# NeuroWing.net
KiCad netlist of a schematic drawn in EAGLE
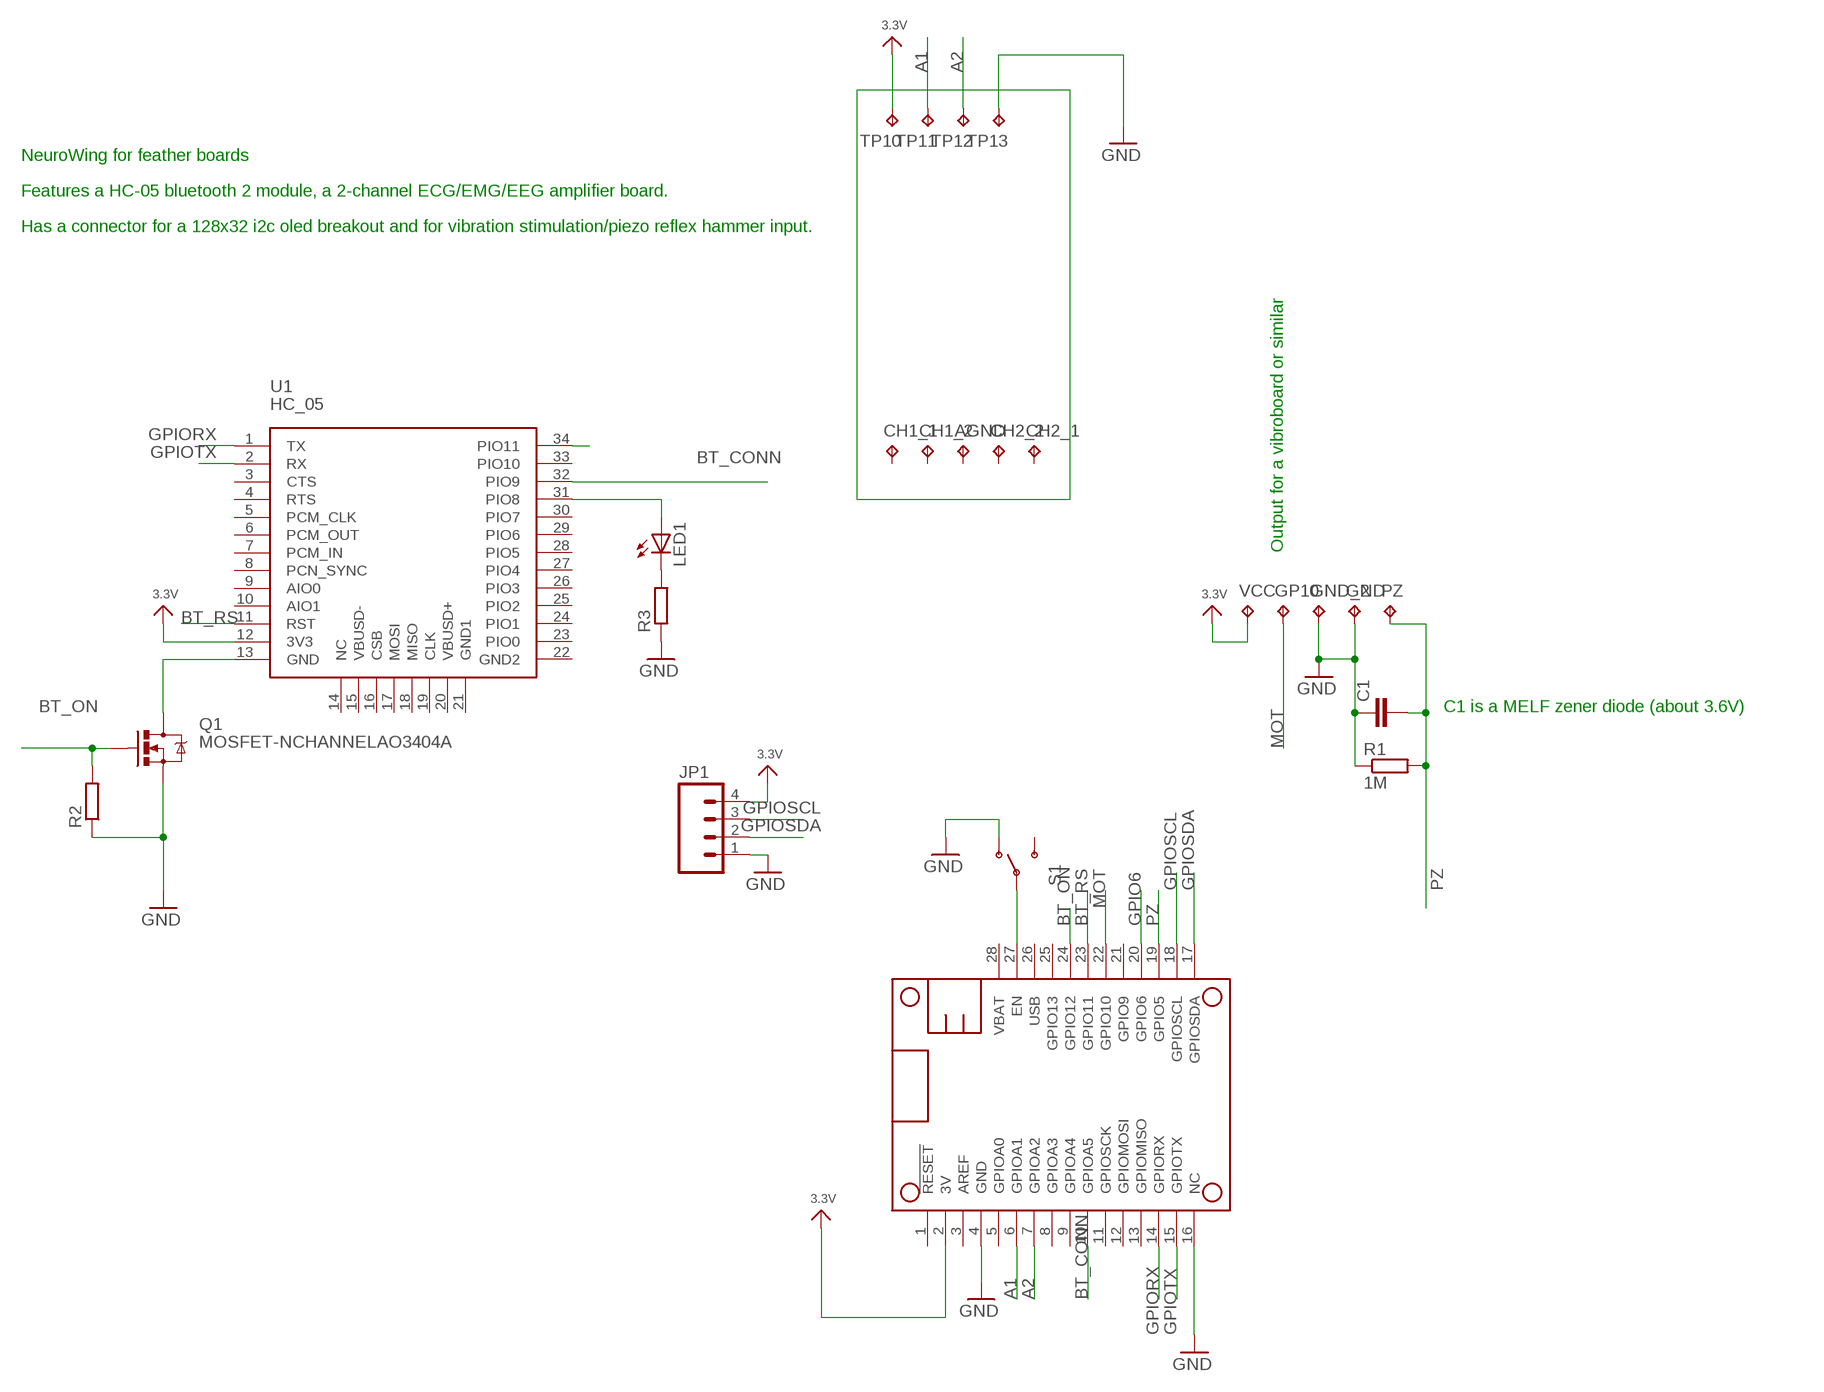
[diagram p0: schematic, sheet 1]

(export (version "E")
  (design (tool "Eeschema 10.0.6"))
  (components
    (comp (ref "AGND")
      (value "TPTP17R")
      (footprint "eagle-import:TP17R")
      (libsource (lib "eagle-import") (part "TPTP17R"))
    )
    (comp (ref "C1")
      (value "C-EUC1206")
      (footprint "eagle-import:C1206")
      (libsource (lib "eagle-import") (part "C-EUC1206"))
    )
    (comp (ref "CH1_1")
      (value "TPTP17R")
      (footprint "eagle-import:TP17R")
      (libsource (lib "eagle-import") (part "TPTP17R"))
    )
    (comp (ref "CH1_2")
      (value "TPTP17R")
      (footprint "eagle-import:TP17R")
      (libsource (lib "eagle-import") (part "TPTP17R"))
    )
    (comp (ref "CH2_1")
      (value "TPTP17R")
      (footprint "eagle-import:TP17R")
      (libsource (lib "eagle-import") (part "TPTP17R"))
    )
    (comp (ref "CH2_2")
      (value "TPTP17R")
      (footprint "eagle-import:TP17R")
      (libsource (lib "eagle-import") (part "TPTP17R"))
    )
    (comp (ref "GND")
      (value "TPTP20R")
      (footprint "eagle-import:TP20R")
      (libsource (lib "eagle-import") (part "TPTP20R"))
    )
    (comp (ref "GND_2")
      (value "TPTP20R")
      (footprint "eagle-import:TP20R")
      (libsource (lib "eagle-import") (part "TPTP20R"))
    )
    (comp (ref "GP10")
      (value "TPTP20R")
      (footprint "eagle-import:TP20R")
      (libsource (lib "eagle-import") (part "TPTP20R"))
    )
    (comp (ref "JP1")
      (value "M04PTH")
      (footprint "eagle-import:1X04")
      (libsource (lib "eagle-import") (part "M04PTH"))
    )
    (comp (ref "LED1")
      (value "LEDCHIP-LED0805")
      (footprint "eagle-import:CHIP-LED0805")
      (libsource (lib "eagle-import") (part "LEDCHIP-LED0805"))
    )
    (comp (ref "MS2")
      (value "FEATHERWING")
      (footprint "eagle-import:FEATHERWING")
      (libsource (lib "eagle-import") (part "FEATHERWING"))
    )
    (comp (ref "PZ")
      (value "TPTP20R")
      (footprint "eagle-import:TP20R")
      (libsource (lib "eagle-import") (part "TPTP20R"))
    )
    (comp (ref "Q1")
      (value "MOSFET-NCHANNELAO3404A")
      (footprint "eagle-import:SOT23-3")
      (libsource (lib "eagle-import") (part "MOSFET-NCHANNELAO3404A"))
    )
    (comp (ref "R1")
      (value "1M")
      (footprint "eagle-import:R0603")
      (libsource (lib "eagle-import") (part "R-EU_R0603"))
    )
    (comp (ref "R2")
      (value "R-EU_R0603")
      (footprint "eagle-import:R0603")
      (libsource (lib "eagle-import") (part "R-EU_R0603"))
    )
    (comp (ref "R3")
      (value "R-EU_R0603")
      (footprint "eagle-import:R0603")
      (libsource (lib "eagle-import") (part "R-EU_R0603"))
    )
    (comp (ref "S1")
      (value "SWITCH-SPDT-SMD-A")
      (footprint "eagle-import:SWITCH-SPST-SMD-A")
      (libsource (lib "eagle-import") (part "SWITCH-SPDT-SMD-A"))
    )
    (comp (ref "TP10")
      (value "TPTP17R")
      (footprint "eagle-import:TP17R")
      (libsource (lib "eagle-import") (part "TPTP17R"))
    )
    (comp (ref "TP11")
      (value "TPTP17R")
      (footprint "eagle-import:TP17R")
      (libsource (lib "eagle-import") (part "TPTP17R"))
    )
    (comp (ref "TP12")
      (value "TPTP17R")
      (footprint "eagle-import:TP17R")
      (libsource (lib "eagle-import") (part "TPTP17R"))
    )
    (comp (ref "TP13")
      (value "TPTP17R")
      (footprint "eagle-import:TP17R")
      (libsource (lib "eagle-import") (part "TPTP17R"))
    )
    (comp (ref "U1")
      (value "HC_05")
      (footprint "eagle-import:BLUETOOTH_SMD")
      (libsource (lib "eagle-import") (part "HC_05"))
    )
    (comp (ref "VCC")
      (value "TPTP20R")
      (footprint "eagle-import:TP20R")
      (libsource (lib "eagle-import") (part "TPTP20R"))
    )
  )
  (nets
    (net (code "1") (name "/A1") (class "Default")
      (node (ref "MS2") (pin "6") (pinfunction "GPIOA1_6") (pintype "bidirectional"))
      (node (ref "TP11") (pin "TP") (pinfunction "TP_TP") (pintype "input"))
    )
    (net (code "2") (name "/A2") (class "Default")
      (node (ref "MS2") (pin "7") (pinfunction "GPIOA2_7") (pintype "bidirectional"))
      (node (ref "TP12") (pin "TP") (pinfunction "TP_TP") (pintype "input"))
    )
    (net (code "3") (name "/BT_CONN") (class "Default")
      (node (ref "MS2") (pin "10") (pinfunction "GPIOA5_10") (pintype "bidirectional"))
      (node (ref "U1") (pin "32") (pinfunction "PIO9_32") (pintype "bidirectional"))
    )
    (net (code "4") (name "/BT_ON") (class "Default")
      (node (ref "MS2") (pin "24") (pinfunction "GPIO12_24") (pintype "bidirectional"))
      (node (ref "Q1") (pin "1") (pinfunction "G_1") (pintype "passive"))
      (node (ref "R2") (pin "2") (pinfunction "2_2") (pintype "passive"))
    )
    (net (code "5") (name "/BT_RS") (class "Default")
      (node (ref "MS2") (pin "23") (pinfunction "GPIO11_23") (pintype "bidirectional"))
      (node (ref "U1") (pin "11") (pinfunction "RST_11") (pintype "bidirectional"))
    )
    (net (code "6") (name "/GPIO6") (class "Default")
      (node (ref "MS2") (pin "20") (pinfunction "GPIO6_20") (pintype "bidirectional"))
    )
    (net (code "7") (name "/GPIORX") (class "Default")
      (node (ref "MS2") (pin "14") (pinfunction "GPIORX_14") (pintype "bidirectional"))
      (node (ref "U1") (pin "1") (pinfunction "TX_1") (pintype "bidirectional"))
    )
    (net (code "8") (name "/GPIOSCL") (class "Default")
      (node (ref "JP1") (pin "3") (pinfunction "3_3") (pintype "passive"))
      (node (ref "MS2") (pin "18") (pinfunction "GPIOSCL_18") (pintype "bidirectional"))
    )
    (net (code "9") (name "/GPIOSDA") (class "Default")
      (node (ref "JP1") (pin "2") (pinfunction "2_2") (pintype "passive"))
      (node (ref "MS2") (pin "17") (pinfunction "GPIOSDA_17") (pintype "bidirectional"))
    )
    (net (code "10") (name "/GPIOTX") (class "Default")
      (node (ref "MS2") (pin "15") (pinfunction "GPIOTX_15") (pintype "bidirectional"))
      (node (ref "U1") (pin "2") (pinfunction "RX_2") (pintype "bidirectional"))
    )
    (net (code "11") (name "/MOT") (class "Default")
      (node (ref "GP10") (pin "TP") (pinfunction "TP_TP") (pintype "input"))
      (node (ref "MS2") (pin "22") (pinfunction "GPIO10_22") (pintype "bidirectional"))
    )
    (net (code "12") (name "/PZ") (class "Default")
      (node (ref "C1") (pin "2") (pinfunction "2_2") (pintype "passive"))
      (node (ref "MS2") (pin "19") (pinfunction "GPIO5_19") (pintype "bidirectional"))
      (node (ref "PZ") (pin "TP") (pinfunction "TP_TP") (pintype "input"))
      (node (ref "R1") (pin "2") (pinfunction "2_2") (pintype "passive"))
    )
    (net (code "13") (name "/USB") (class "Default")
      (node (ref "MS2") (pin "26") (pinfunction "USB_26") (pintype "power_in"))
    )
    (net (code "14") (name "/VBAT") (class "Default")
      (node (ref "MS2") (pin "28") (pinfunction "VBAT_28") (pintype "power_in"))
    )
    (net (code "15") (name "3.3V") (class "Default")
      (node (ref "JP1") (pin "4") (pinfunction "4_4") (pintype "passive"))
      (node (ref "MS2") (pin "2") (pinfunction "3V_2") (pintype "power_in"))
      (node (ref "TP10") (pin "TP") (pinfunction "TP_TP") (pintype "input"))
      (node (ref "U1") (pin "12") (pinfunction "3V3_12") (pintype "bidirectional"))
      (node (ref "VCC") (pin "TP") (pinfunction "TP_TP") (pintype "input"))
    )
    (net (code "16") (name "GND") (class "Default")
      (node (ref "C1") (pin "1") (pinfunction "1_1") (pintype "passive"))
      (node (ref "GND") (pin "TP") (pinfunction "TP_TP") (pintype "input"))
      (node (ref "GND_2") (pin "TP") (pinfunction "TP_TP") (pintype "input"))
      (node (ref "JP1") (pin "1") (pinfunction "1_1") (pintype "passive"))
      (node (ref "MS2") (pin "16") (pinfunction "NC_16") (pintype "passive"))
      (node (ref "MS2") (pin "4") (pinfunction "GND_4") (pintype "power_in"))
      (node (ref "Q1") (pin "2") (pinfunction "S_2") (pintype "passive"))
      (node (ref "R1") (pin "1") (pinfunction "1_1") (pintype "passive"))
      (node (ref "R2") (pin "1") (pinfunction "1_1") (pintype "passive"))
      (node (ref "R3") (pin "1") (pinfunction "1_1") (pintype "passive"))
      (node (ref "S1") (pin "1") (pinfunction "O_1") (pintype "passive"))
      (node (ref "TP13") (pin "TP") (pinfunction "TP_TP") (pintype "input"))
    )
    (net (code "17") (name "Net-(LED1-PadC)") (class "Default")
      (node (ref "LED1") (pin "C") (pinfunction "C_C") (pintype "passive"))
      (node (ref "R3") (pin "2") (pinfunction "2_2") (pintype "passive"))
    )
    (net (code "18") (name "Net-(MS2-EN)") (class "Default")
      (node (ref "MS2") (pin "27") (pinfunction "EN_27") (pintype "passive"))
      (node (ref "S1") (pin "2") (pinfunction "P_2") (pintype "passive"))
    )
    (net (code "19") (name "Net-(Q1-D)") (class "Default")
      (node (ref "Q1") (pin "3") (pinfunction "D_3") (pintype "passive"))
      (node (ref "U1") (pin "13") (pinfunction "GND_13") (pintype "bidirectional"))
    )
    (net (code "20") (name "Net-(U1-PIO8)") (class "Default")
      (node (ref "LED1") (pin "A") (pinfunction "A_A") (pintype "passive"))
      (node (ref "U1") (pin "31") (pinfunction "PIO8_31") (pintype "bidirectional"))
    )
    (net (code "21") (name "unconnected-(AGND-PadTP)") (class "Default")
      (node (ref "AGND") (pin "TP") (pinfunction "TP_TP") (pintype "input"))
    )
    (net (code "22") (name "unconnected-(CH1_1-PadTP)") (class "Default")
      (node (ref "CH1_1") (pin "TP") (pinfunction "TP_TP") (pintype "input"))
    )
    (net (code "23") (name "unconnected-(CH1_2-PadTP)") (class "Default")
      (node (ref "CH1_2") (pin "TP") (pinfunction "TP_TP") (pintype "input"))
    )
    (net (code "24") (name "unconnected-(CH2_1-PadTP)") (class "Default")
      (node (ref "CH2_1") (pin "TP") (pinfunction "TP_TP") (pintype "input"))
    )
    (net (code "25") (name "unconnected-(CH2_2-PadTP)") (class "Default")
      (node (ref "CH2_2") (pin "TP") (pinfunction "TP_TP") (pintype "input"))
    )
    (net (code "26") (name "unconnected-(MS2-AREF-Pad3)") (class "Default")
      (node (ref "MS2") (pin "3") (pinfunction "AREF_3") (pintype "passive"))
    )
    (net (code "27") (name "unconnected-(MS2-GPIO9-Pad21)") (class "Default")
      (node (ref "MS2") (pin "21") (pinfunction "GPIO9_21") (pintype "bidirectional"))
    )
    (net (code "28") (name "unconnected-(MS2-GPIO13-Pad25)") (class "Default")
      (node (ref "MS2") (pin "25") (pinfunction "GPIO13_25") (pintype "bidirectional"))
    )
    (net (code "29") (name "unconnected-(MS2-GPIOA0-Pad5)") (class "Default")
      (node (ref "MS2") (pin "5") (pinfunction "GPIOA0_5") (pintype "bidirectional"))
    )
    (net (code "30") (name "unconnected-(MS2-GPIOA3-Pad8)") (class "Default")
      (node (ref "MS2") (pin "8") (pinfunction "GPIOA3_8") (pintype "bidirectional"))
    )
    (net (code "31") (name "unconnected-(MS2-GPIOA4-Pad9)") (class "Default")
      (node (ref "MS2") (pin "9") (pinfunction "GPIOA4_9") (pintype "bidirectional"))
    )
    (net (code "32") (name "unconnected-(MS2-GPIOMISO-Pad13)") (class "Default")
      (node (ref "MS2") (pin "13") (pinfunction "GPIOMISO_13") (pintype "bidirectional"))
    )
    (net (code "33") (name "unconnected-(MS2-GPIOMOSI-Pad12)") (class "Default")
      (node (ref "MS2") (pin "12") (pinfunction "GPIOMOSI_12") (pintype "bidirectional"))
    )
    (net (code "34") (name "unconnected-(MS2-GPIOSCK-Pad11)") (class "Default")
      (node (ref "MS2") (pin "11") (pinfunction "GPIOSCK_11") (pintype "bidirectional"))
    )
    (net (code "35") (name "unconnected-(MS2-~{RESET}-Pad1)") (class "Default")
      (node (ref "MS2") (pin "1") (pinfunction "~{RESET}_1") (pintype "input"))
    )
    (net (code "36") (name "unconnected-(S1-S-Pad3)") (class "Default")
      (node (ref "S1") (pin "3") (pinfunction "S_3") (pintype "passive"))
    )
    (net (code "37") (name "unconnected-(U1-AIO0-Pad9)") (class "Default")
      (node (ref "U1") (pin "9") (pinfunction "AIO0_9") (pintype "bidirectional"))
    )
    (net (code "38") (name "unconnected-(U1-AIO1-Pad10)") (class "Default")
      (node (ref "U1") (pin "10") (pinfunction "AIO1_10") (pintype "bidirectional"))
    )
    (net (code "39") (name "unconnected-(U1-CLK-Pad19)") (class "Default")
      (node (ref "U1") (pin "19") (pinfunction "CLK_19") (pintype "bidirectional"))
    )
    (net (code "40") (name "unconnected-(U1-CSB-Pad16)") (class "Default")
      (node (ref "U1") (pin "16") (pinfunction "CSB_16") (pintype "bidirectional"))
    )
    (net (code "41") (name "unconnected-(U1-CTS-Pad3)") (class "Default")
      (node (ref "U1") (pin "3") (pinfunction "CTS_3") (pintype "bidirectional"))
    )
    (net (code "42") (name "unconnected-(U1-GND1-Pad21)") (class "Default")
      (node (ref "U1") (pin "21") (pinfunction "GND1_21") (pintype "bidirectional"))
    )
    (net (code "43") (name "unconnected-(U1-GND2-Pad22)") (class "Default")
      (node (ref "U1") (pin "22") (pinfunction "GND2_22") (pintype "bidirectional"))
    )
    (net (code "44") (name "unconnected-(U1-MISO-Pad18)") (class "Default")
      (node (ref "U1") (pin "18") (pinfunction "MISO_18") (pintype "bidirectional"))
    )
    (net (code "45") (name "unconnected-(U1-MOSI-Pad17)") (class "Default")
      (node (ref "U1") (pin "17") (pinfunction "MOSI_17") (pintype "bidirectional"))
    )
    (net (code "46") (name "unconnected-(U1-NC-Pad14)") (class "Default")
      (node (ref "U1") (pin "14") (pinfunction "NC_14") (pintype "bidirectional"))
    )
    (net (code "47") (name "unconnected-(U1-PCM_CLK-Pad5)") (class "Default")
      (node (ref "U1") (pin "5") (pinfunction "PCM_CLK_5") (pintype "bidirectional"))
    )
    (net (code "48") (name "unconnected-(U1-PCM_IN-Pad7)") (class "Default")
      (node (ref "U1") (pin "7") (pinfunction "PCM_IN_7") (pintype "bidirectional"))
    )
    (net (code "49") (name "unconnected-(U1-PCM_OUT-Pad6)") (class "Default")
      (node (ref "U1") (pin "6") (pinfunction "PCM_OUT_6") (pintype "bidirectional"))
    )
    (net (code "50") (name "unconnected-(U1-PCN_SYNC-Pad8)") (class "Default")
      (node (ref "U1") (pin "8") (pinfunction "PCN_SYNC_8") (pintype "bidirectional"))
    )
    (net (code "51") (name "unconnected-(U1-PIO0-Pad23)") (class "Default")
      (node (ref "U1") (pin "23") (pinfunction "PIO0_23") (pintype "bidirectional"))
    )
    (net (code "52") (name "unconnected-(U1-PIO1-Pad24)") (class "Default")
      (node (ref "U1") (pin "24") (pinfunction "PIO1_24") (pintype "bidirectional"))
    )
    (net (code "53") (name "unconnected-(U1-PIO2-Pad25)") (class "Default")
      (node (ref "U1") (pin "25") (pinfunction "PIO2_25") (pintype "bidirectional"))
    )
    (net (code "54") (name "unconnected-(U1-PIO3-Pad26)") (class "Default")
      (node (ref "U1") (pin "26") (pinfunction "PIO3_26") (pintype "bidirectional"))
    )
    (net (code "55") (name "unconnected-(U1-PIO4-Pad27)") (class "Default")
      (node (ref "U1") (pin "27") (pinfunction "PIO4_27") (pintype "bidirectional"))
    )
    (net (code "56") (name "unconnected-(U1-PIO5-Pad28)") (class "Default")
      (node (ref "U1") (pin "28") (pinfunction "PIO5_28") (pintype "bidirectional"))
    )
    (net (code "57") (name "unconnected-(U1-PIO6-Pad29)") (class "Default")
      (node (ref "U1") (pin "29") (pinfunction "PIO6_29") (pintype "bidirectional"))
    )
    (net (code "58") (name "unconnected-(U1-PIO7-Pad30)") (class "Default")
      (node (ref "U1") (pin "30") (pinfunction "PIO7_30") (pintype "bidirectional"))
    )
    (net (code "59") (name "unconnected-(U1-PIO10-Pad33)") (class "Default")
      (node (ref "U1") (pin "33") (pinfunction "PIO10_33") (pintype "bidirectional"))
    )
    (net (code "60") (name "unconnected-(U1-PIO11-Pad34)") (class "Default")
      (node (ref "U1") (pin "34") (pinfunction "PIO11_34") (pintype "bidirectional"))
    )
    (net (code "61") (name "unconnected-(U1-RTS-Pad4)") (class "Default")
      (node (ref "U1") (pin "4") (pinfunction "RTS_4") (pintype "bidirectional"))
    )
    (net (code "62") (name "unconnected-(U1-VBUSD+-Pad20)") (class "Default")
      (node (ref "U1") (pin "20") (pinfunction "VBUSD+_20") (pintype "bidirectional"))
    )
    (net (code "63") (name "unconnected-(U1-VBUSD--Pad15)") (class "Default")
      (node (ref "U1") (pin "15") (pinfunction "VBUSD-_15") (pintype "bidirectional"))
    )
  )
)
